# Power.net
KiCad netlist of a schematic drawn in Altium Designer
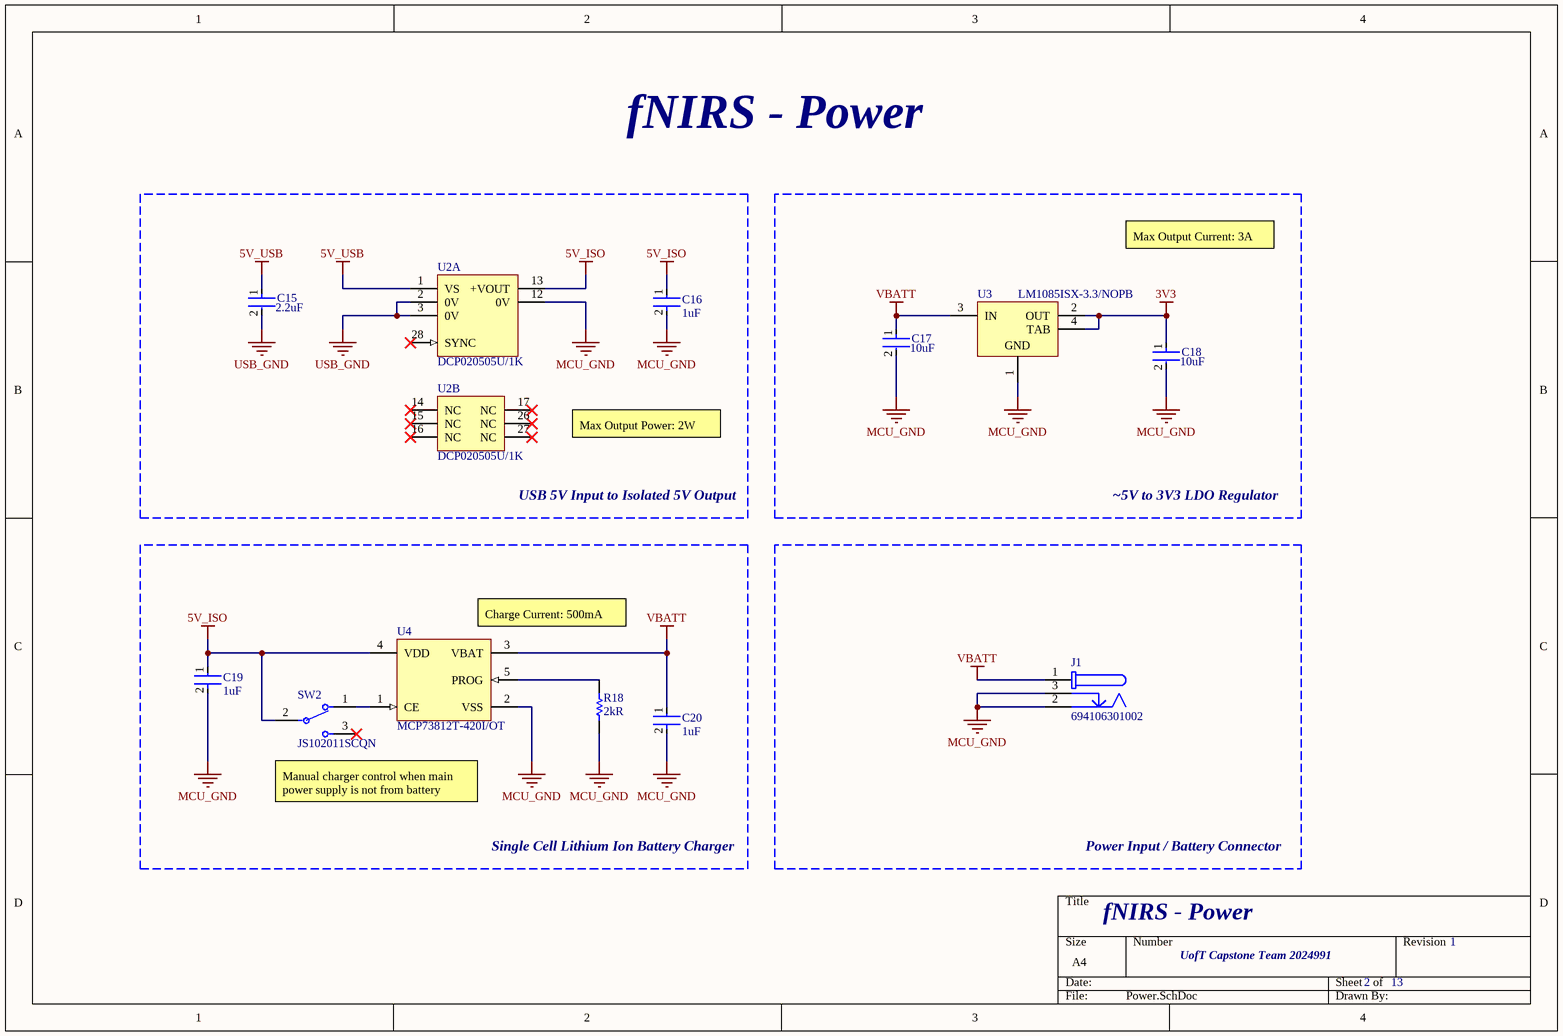
[diagram p0: Power.SchDoc]

(export (version "E")
  (design (tool "Eeschema 10.0.6"))
  (components
    (comp (ref "C15")
      (value "GRM188R61E225KA12D")
      (footprint "FP-GRM188-0_1-e0_2_0_5-MFG")
      (description "Chip Multilayer Ceramic Capacitors for General Purpose, 0603, 2.2uF, X5R, 15%, 10%, 25V")
      (fields
        (field (name "TOLERANCE") "10%")
        (field (name "VOLTAGE") "25V")
        (field (name "CAPACITANCE") "2.2uF")
      )
      (libsource (lib "Altium Content Vault") (part "11868f565c42a9108669ba33697ecf6"))
    )
    (comp (ref "C16")
      (value "C1608X5R1H105K080AB")
      (footprint "FP-C1608-080-0_1-IPC_B")
      (description "Multilayer Ceramic Capacitors 1μF ±10% 50V X5R SMD 0603")
      (fields
        (field (name "VOLTAGE") "50V")
        (field (name "CAPACITANCE") "1uF")
        (field (name "TOLERANCE") "10%")
      )
      (libsource (lib "Altium Content Vault") (part "236180d848d6139a670b325ea6854c9"))
    )
    (comp (ref "C17")
      (value "GRM188R61E106MA73D")
      (footprint "FP-GRM188-0_2-MFG")
      (description "Chip Multilayer Ceramic Capacitors for General Purpose, 0603, 10uF, X5R, 15%, 20%, 25V")
      (fields
        (field (name "TOLERANCE") "20%")
        (field (name "VOLTAGE") "25V")
        (field (name "CAPACITANCE") "10uF")
      )
      (libsource (lib "Altium Content Vault") (part "11868f565c42a9108669ba33697ecf6"))
    )
    (comp (ref "C18")
      (value "GRM188R61E106MA73D")
      (footprint "FP-GRM188-0_2-MFG")
      (description "Chip Multilayer Ceramic Capacitors for General Purpose, 0603, 10uF, X5R, 15%, 20%, 25V")
      (fields
        (field (name "TOLERANCE") "20%")
        (field (name "VOLTAGE") "25V")
        (field (name "CAPACITANCE") "10uF")
      )
      (libsource (lib "Altium Content Vault") (part "11868f565c42a9108669ba33697ecf6"))
    )
    (comp (ref "C19")
      (value "C1608X5R1H105K080AB")
      (footprint "FP-C1608-080-0_1-IPC_B")
      (description "Multilayer Ceramic Capacitors 1μF ±10% 50V X5R SMD 0603")
      (fields
        (field (name "VOLTAGE") "50V")
        (field (name "CAPACITANCE") "1uF")
        (field (name "TOLERANCE") "10%")
      )
      (libsource (lib "Altium Content Vault") (part "236180d848d6139a670b325ea6854c9"))
    )
    (comp (ref "C20")
      (value "C1608X5R1H105K080AB")
      (footprint "FP-C1608-080-0_1-IPC_B")
      (description "Multilayer Ceramic Capacitors 1μF ±10% 50V X5R SMD 0603")
      (fields
        (field (name "VOLTAGE") "50V")
        (field (name "CAPACITANCE") "1uF")
        (field (name "TOLERANCE") "10%")
      )
      (libsource (lib "Altium Content Vault") (part "236180d848d6139a670b325ea6854c9"))
    )
    (comp (ref "J1")
      (value "694106301002")
      (footprint "694106301002")
      (libsource (lib "Altium Content Vault") (part "DC Power Jack"))
    )
    (comp (ref "R18")
      (value "CRCW06032K00FKEA")
      (footprint "RESC1609X50X30ML10T20")
      (fields (field (name "MANUFACTURER") "Vishay Dale") (field (name "RESISTANCE") "2kR"))
      (libsource (lib "Altium Content Vault") (part "RES"))
    )
    (comp (ref "SW2")
      (value "JS102011SCQN")
      (footprint "FP-JS102011SCQN-MFG")
      (description "SWITCH SLIDE SPDT 300MA 6V")
      (libsource (lib "Altium Content Vault") (part "39e195cbbadc85d1df0d7eb6847d379"))
    )
    (comp (ref "U2")
      (value "DCP020505U/1K")
      (footprint "DVB0012A_L")
      (fields (field (name "MANUFACTURER") "Texas Instruments"))
      (libsource (lib "Altium Content Vault") (part "TI-DCP02XXXXDVB12"))
    )
    (comp (ref "U3")
      (value "LM1085ISX-3.3/NOPB")
      (footprint "KTT0003B_M")
      (description "3A Low Dropout Positive Regulators, 3-pin TO-263, Pb-Free")
      (fields (field (name "MANUFACTURER") "Texas Instruments"))
      (libsource (lib "Altium Content Vault") (part "PM-REG-LM1086-SOT4"))
    )
    (comp (ref "U4")
      (value "MCP73812T-420I/OT")
      (footprint "SOT-23-OT5_M")
      (libsource (lib "Altium Content Vault") (part "PM-BM-MCP7381X-SOT5"))
    )
  )
  (nets
    (net (code "1") (name "3V3") (class "Default")
      (node (ref "C18") (pin "1") (pinfunction "1_1") (pintype "passive"))
      (node (ref "U3") (pin "2") (pinfunction "OUT_2") (pintype "power_in"))
      (node (ref "U3") (pin "4") (pinfunction "TAB_4") (pintype "power_in"))
    )
    (net (code "2") (name "5V_ISO") (class "Default")
      (node (ref "C16") (pin "1") (pinfunction "1_1") (pintype "passive"))
      (node (ref "C19") (pin "1") (pinfunction "1_1") (pintype "passive"))
      (node (ref "SW2") (pin "2") (pinfunction "C_2") (pintype "passive"))
      (node (ref "U2") (pin "13") (pinfunction "+VOUT_13") (pintype "power_in"))
      (node (ref "U4") (pin "4") (pinfunction "VDD_4") (pintype "power_in"))
    )
    (net (code "3") (name "5V_USB") (class "Default")
      (node (ref "C15") (pin "1") (pinfunction "1_1") (pintype "passive"))
      (node (ref "U2") (pin "1") (pinfunction "VS_1") (pintype "power_in"))
    )
    (net (code "4") (name "MCU_GND") (class "Default")
      (node (ref "C16") (pin "2") (pinfunction "2_2") (pintype "passive"))
      (node (ref "C17") (pin "2") (pinfunction "2_2") (pintype "passive"))
      (node (ref "C18") (pin "2") (pinfunction "2_2") (pintype "passive"))
      (node (ref "C19") (pin "2") (pinfunction "2_2") (pintype "passive"))
      (node (ref "C20") (pin "2") (pinfunction "2_2") (pintype "passive"))
      (node (ref "J1") (pin "2") (pinfunction "2_2") (pintype "passive"))
      (node (ref "J1") (pin "3") (pinfunction "3_3") (pintype "passive"))
      (node (ref "R18") (pin "1") (pinfunction "1_1") (pintype "passive"))
      (node (ref "U2") (pin "12") (pinfunction "0V_12") (pintype "power_in"))
      (node (ref "U3") (pin "1") (pinfunction "GND_1") (pintype "power_in"))
      (node (ref "U4") (pin "2") (pinfunction "VSS_2") (pintype "power_in"))
    )
    (net (code "5") (name "Net-(U4-CE)") (class "Default")
      (node (ref "SW2") (pin "1") (pinfunction "1_1") (pintype "passive"))
      (node (ref "U4") (pin "1") (pinfunction "CE_1") (pintype "input"))
    )
    (net (code "6") (name "Net-(U4-PROG)") (class "Default")
      (node (ref "R18") (pin "2") (pinfunction "2_2") (pintype "passive"))
      (node (ref "U4") (pin "5") (pinfunction "PROG_5") (pintype "input"))
    )
    (net (code "7") (name "USB_GND") (class "Default")
      (node (ref "C15") (pin "2") (pinfunction "2_2") (pintype "passive"))
      (node (ref "U2") (pin "2") (pinfunction "0V_2") (pintype "power_in"))
      (node (ref "U2") (pin "3") (pinfunction "0V_3") (pintype "power_in"))
    )
    (net (code "8") (name "VBATT") (class "Default")
      (node (ref "C17") (pin "1") (pinfunction "1_1") (pintype "passive"))
      (node (ref "C20") (pin "1") (pinfunction "1_1") (pintype "passive"))
      (node (ref "J1") (pin "1") (pinfunction "1_1") (pintype "passive"))
      (node (ref "U3") (pin "3") (pinfunction "IN_3") (pintype "power_in"))
      (node (ref "U4") (pin "3") (pinfunction "VBAT_3") (pintype "power_in"))
    )
    (net (code "9") (name "unconnected-(SW2-Pad3)") (class "Default")
      (node (ref "SW2") (pin "3") (pinfunction "3_3") (pintype "passive+no_connect"))
    )
    (net (code "10") (name "unconnected-(U2A-SYNC-Pad28)") (class "Default")
      (node (ref "U2") (pin "28") (pinfunction "SYNC_28") (pintype "input+no_connect"))
    )
    (net (code "11") (name "unconnected-(U2B-NC-Pad14)") (class "Default")
      (node (ref "U2") (pin "14") (pinfunction "NC_14") (pintype "passive+no_connect"))
    )
    (net (code "12") (name "unconnected-(U2B-NC-Pad15)") (class "Default")
      (node (ref "U2") (pin "15") (pinfunction "NC_15") (pintype "passive+no_connect"))
    )
    (net (code "13") (name "unconnected-(U2B-NC-Pad16)") (class "Default")
      (node (ref "U2") (pin "16") (pinfunction "NC_16") (pintype "passive+no_connect"))
    )
    (net (code "14") (name "unconnected-(U2B-NC-Pad17)") (class "Default")
      (node (ref "U2") (pin "17") (pinfunction "NC_17") (pintype "passive+no_connect"))
    )
    (net (code "15") (name "unconnected-(U2B-NC-Pad26)") (class "Default")
      (node (ref "U2") (pin "26") (pinfunction "NC_26") (pintype "passive+no_connect"))
    )
    (net (code "16") (name "unconnected-(U2B-NC-Pad27)") (class "Default")
      (node (ref "U2") (pin "27") (pinfunction "NC_27") (pintype "passive+no_connect"))
    )
  )
)
